# Alimentacion.net
KiCad netlist of a schematic drawn in Altium Designer
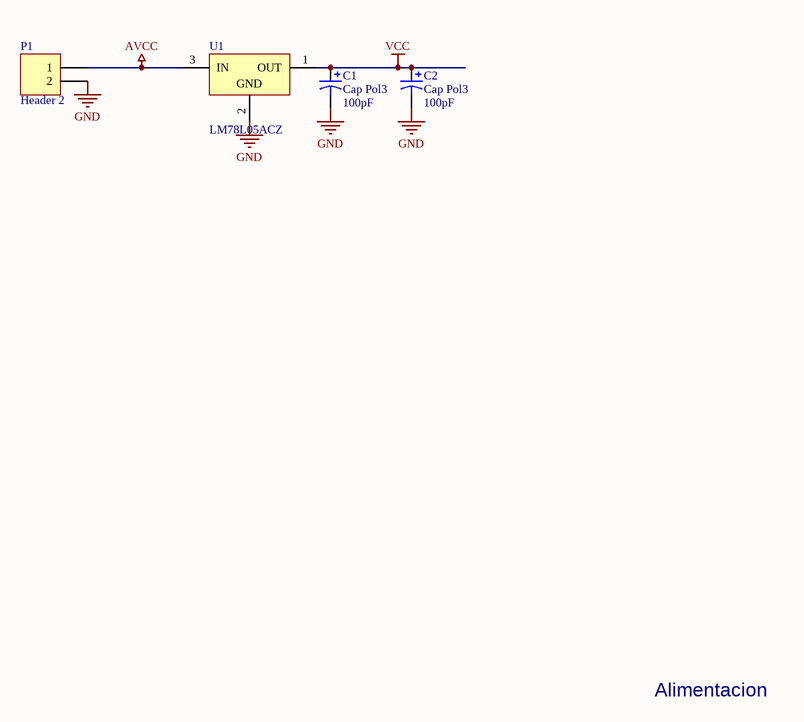
[diagram p0: Alimentacion.SchDoc]

(export (version "E")
  (design (tool "Eeschema 10.0.6"))
  (components
    (comp (ref "C1")
      (value "Cap Pol3")
      (footprint "C0805")
      (description "Polarized Capacitor (Surface Mount)")
      (fields (field (name "ALTIUM_VALUE") "100pF") (field (name "PUBLISHER") "Altium Limited"))
      (libsource (lib "Miscellaneous Devices") (part "Cap Pol3"))
    )
    (comp (ref "C2")
      (value "Cap Pol3")
      (footprint "C0805")
      (description "Polarized Capacitor (Surface Mount)")
      (fields (field (name "ALTIUM_VALUE") "100pF") (field (name "PUBLISHER") "Altium Limited"))
      (libsource (lib "Miscellaneous Devices") (part "Cap Pol3"))
    )
    (comp (ref "P1")
      (value "Header 2")
      (footprint "HDR1X2")
      (description "Header, 2-Pin")
      (fields (field (name "PUBLISHER") "Altium Limited"))
      (libsource (lib "Miscellaneous Connectors") (part "Header 2"))
    )
    (comp (ref "U1")
      (value "LM78L05ACZ")
      (footprint "BCY-W3")
      (description "3-Terminal Positive Regulators")
      (fields
        (field (name "MANUFACTURER") "National Semiconductor")
        (field (name "DIGIKEYPARTNUMBER") "LM78L05ACZNS-ND")
        (field (name "PUBLISHER") "Altium Limited")
      )
      (libsource (lib "NSC LDO") (part "LM78L05ACZ"))
    )
  )
  (nets
    (net (code "1") (name "AVCC") (class "Default")
      (node (ref "P1") (pin "1") (pinfunction "1_1") (pintype "passive"))
      (node (ref "U1") (pin "3") (pinfunction "IN_3") (pintype "power_in"))
    )
    (net (code "2") (name "GND") (class "Default")
      (node (ref "C1") (pin "2") (pinfunction "2_2") (pintype "passive"))
      (node (ref "C2") (pin "2") (pinfunction "2_2") (pintype "passive"))
      (node (ref "P1") (pin "2") (pinfunction "2_2") (pintype "passive"))
      (node (ref "U1") (pin "2") (pinfunction "GND_2") (pintype "power_in"))
    )
    (net (code "3") (name "VCC") (class "Default")
      (node (ref "C1") (pin "1") (pinfunction "1_1") (pintype "passive"))
      (node (ref "C2") (pin "1") (pinfunction "1_1") (pintype "passive"))
      (node (ref "U1") (pin "1") (pinfunction "OUT_1") (pintype "power_in"))
    )
  )
)
